# z0-probe-v8.net
KiCad netlist of a schematic drawn in EAGLE
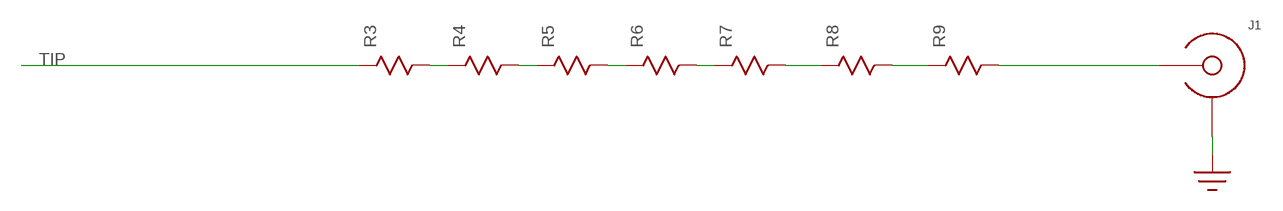
[diagram p0: schematic, sheet 1]

(export (version "E")
  (design (tool "Eeschema 10.0.6"))
  (components
    (comp (ref "J1")
      (value "SMA-EDGE-LAUNCH")
      (footprint "eagle-import:SMA_EDGE_LAUNCH_2L_4020_TAPER_FIXED")
      (libsource (lib "eagle-import") (part "SMA-EDGE-LAUNCH"))
    )
    (comp (ref "R3")
      (value "R0603-TIGHT")
      (footprint "eagle-import:0603_TIGHT")
      (libsource (lib "eagle-import") (part "R0603-TIGHT"))
    )
    (comp (ref "R4")
      (value "R0603-TIGHT")
      (footprint "eagle-import:0603_TIGHT")
      (libsource (lib "eagle-import") (part "R0603-TIGHT"))
    )
    (comp (ref "R5")
      (value "R0603-TIGHT")
      (footprint "eagle-import:0603_TIGHT")
      (libsource (lib "eagle-import") (part "R0603-TIGHT"))
    )
    (comp (ref "R6")
      (value "R0603-TIGHT")
      (footprint "eagle-import:0603_TIGHT")
      (libsource (lib "eagle-import") (part "R0603-TIGHT"))
    )
    (comp (ref "R7")
      (value "R0603-TIGHT")
      (footprint "eagle-import:0603_TIGHT")
      (libsource (lib "eagle-import") (part "R0603-TIGHT"))
    )
    (comp (ref "R8")
      (value "R0603-TIGHT")
      (footprint "eagle-import:0603_TIGHT")
      (libsource (lib "eagle-import") (part "R0603-TIGHT"))
    )
    (comp (ref "R9")
      (value "R0603-TIGHT")
      (footprint "eagle-import:0603_TIGHT")
      (libsource (lib "eagle-import") (part "R0603-TIGHT"))
    )
  )
  (nets
    (net (code "1") (name "/TIP") (class "Default")
      (node (ref "R3") (pin "P$1") (pinfunction "P$3_P$1") (pintype "bidirectional"))
    )
    (net (code "2") (name "GND") (class "Default")
      (node (ref "J1") (pin "BOTTOM_GND") (pinfunction "SHIELD_BOTTOM_GND") (pintype "bidirectional"))
      (node (ref "J1") (pin "GND@1") (pinfunction "SHIELD_GND@1") (pintype "bidirectional"))
      (node (ref "J1") (pin "GND@14") (pinfunction "SHIELD_GND@14") (pintype "bidirectional"))
      (node (ref "J1") (pin "GND@15") (pinfunction "SHIELD_GND@15") (pintype "bidirectional"))
      (node (ref "J1") (pin "GND@16") (pinfunction "SHIELD_GND@16") (pintype "bidirectional"))
      (node (ref "J1") (pin "GND@17") (pinfunction "SHIELD_GND@17") (pintype "bidirectional"))
      (node (ref "J1") (pin "GND@2") (pinfunction "SHIELD_GND@2") (pintype "bidirectional"))
      (node (ref "J1") (pin "GND@3") (pinfunction "SHIELD_GND@3") (pintype "bidirectional"))
      (node (ref "J1") (pin "GND@4") (pinfunction "SHIELD_GND@4") (pintype "bidirectional"))
      (node (ref "J1") (pin "GND@5") (pinfunction "SHIELD_GND@5") (pintype "bidirectional"))
      (node (ref "J1") (pin "GND@6") (pinfunction "SHIELD_GND@6") (pintype "bidirectional"))
      (node (ref "J1") (pin "GND@7") (pinfunction "SHIELD_GND@7") (pintype "bidirectional"))
      (node (ref "J1") (pin "GND@8") (pinfunction "SHIELD_GND@8") (pintype "bidirectional"))
      (node (ref "J1") (pin "GND_PAD1") (pinfunction "SHIELD_GND_PAD1") (pintype "bidirectional"))
      (node (ref "J1") (pin "GND_PAD2") (pinfunction "SHIELD_GND_PAD2") (pintype "bidirectional"))
      (node (ref "J1") (pin "P$1") (pinfunction "SHIELD_P$1") (pintype "bidirectional"))
      (node (ref "J1") (pin "P$2") (pinfunction "SHIELD_P$2") (pintype "bidirectional"))
    )
    (net (code "3") (name "Net-(R3-P$4)") (class "Default")
      (node (ref "R3") (pin "P$2") (pinfunction "P$4_P$2") (pintype "bidirectional"))
      (node (ref "R4") (pin "P$1") (pinfunction "P$3_P$1") (pintype "bidirectional"))
    )
    (net (code "4") (name "Net-(R4-P$4)") (class "Default")
      (node (ref "R4") (pin "P$2") (pinfunction "P$4_P$2") (pintype "bidirectional"))
      (node (ref "R5") (pin "P$1") (pinfunction "P$3_P$1") (pintype "bidirectional"))
    )
    (net (code "5") (name "Net-(R5-P$4)") (class "Default")
      (node (ref "R5") (pin "P$2") (pinfunction "P$4_P$2") (pintype "bidirectional"))
      (node (ref "R6") (pin "P$1") (pinfunction "P$3_P$1") (pintype "bidirectional"))
    )
    (net (code "6") (name "Net-(R6-P$4)") (class "Default")
      (node (ref "R6") (pin "P$2") (pinfunction "P$4_P$2") (pintype "bidirectional"))
      (node (ref "R7") (pin "P$1") (pinfunction "P$3_P$1") (pintype "bidirectional"))
    )
    (net (code "7") (name "Net-(R7-P$4)") (class "Default")
      (node (ref "R7") (pin "P$2") (pinfunction "P$4_P$2") (pintype "bidirectional"))
      (node (ref "R8") (pin "P$1") (pinfunction "P$3_P$1") (pintype "bidirectional"))
    )
    (net (code "8") (name "Net-(R8-P$4)") (class "Default")
      (node (ref "R8") (pin "P$2") (pinfunction "P$4_P$2") (pintype "bidirectional"))
      (node (ref "R9") (pin "P$1") (pinfunction "P$3_P$1") (pintype "bidirectional"))
    )
    (net (code "9") (name "Net-(R9-P$4)") (class "Default")
      (node (ref "J1") (pin "CENTER@1") (pinfunction "CENTER_CENTER@1") (pintype "bidirectional"))
      (node (ref "J1") (pin "P$3") (pinfunction "CENTER_P$3") (pintype "bidirectional"))
      (node (ref "R9") (pin "P$2") (pinfunction "P$4_P$2") (pintype "bidirectional"))
    )
  )
)
